# Controller_PCB_OPAMP.net
KiCad netlist of a schematic drawn in Altium Designer
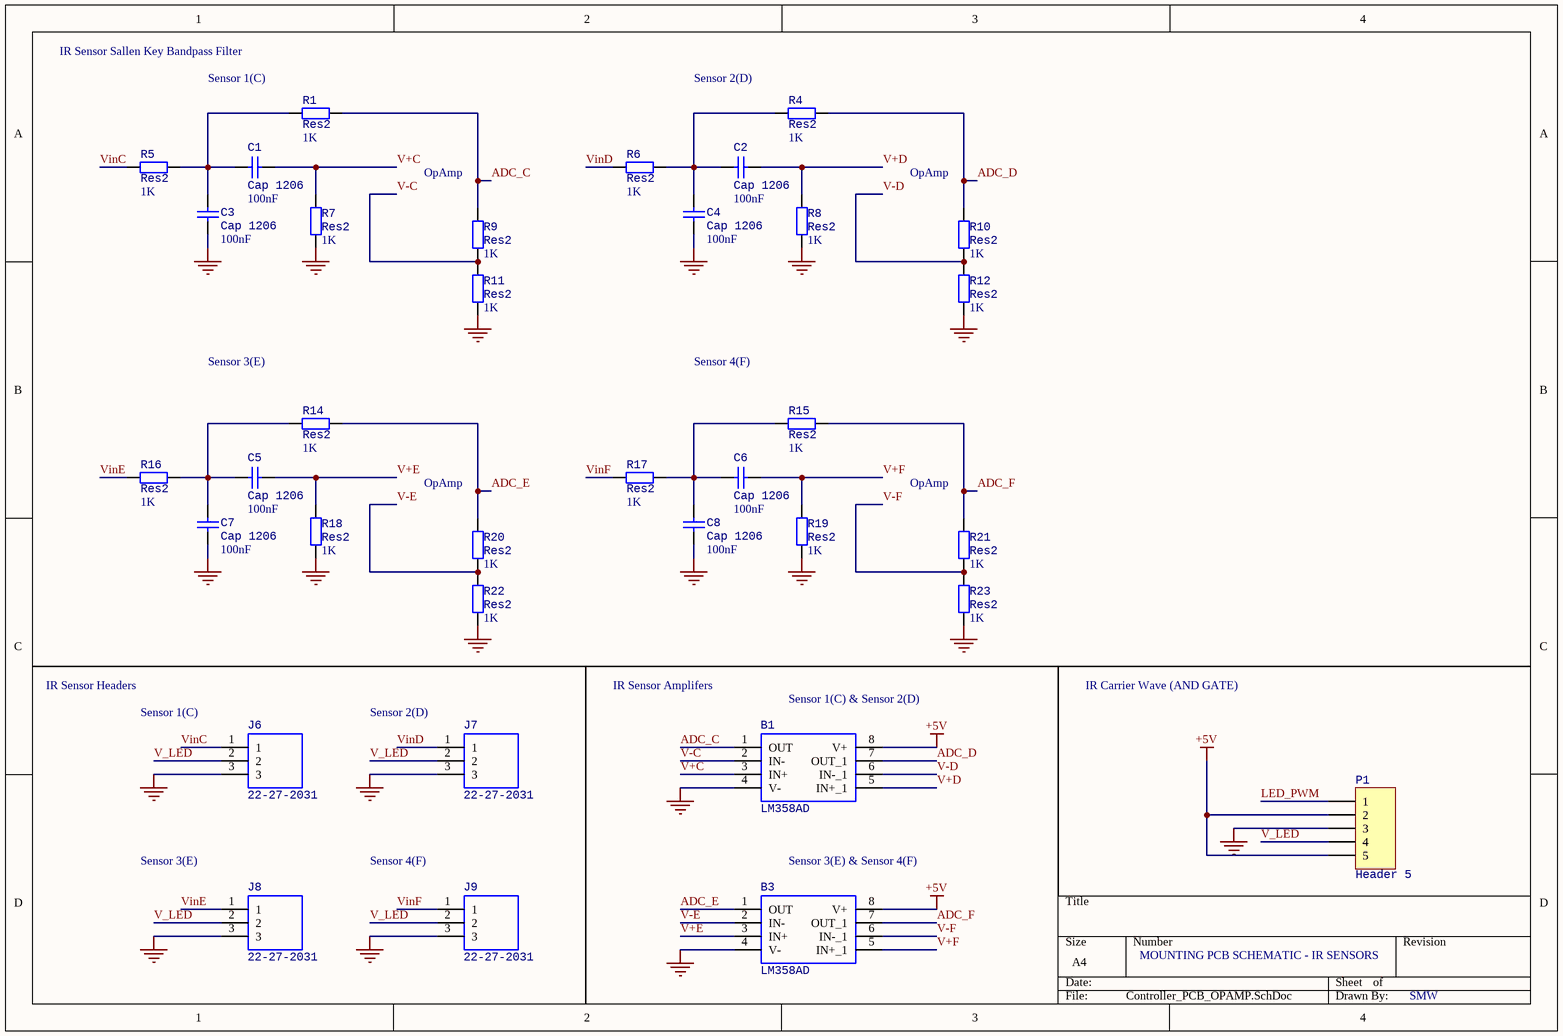
[diagram p0: Controller_PCB_OPAMP.SchDoc]

(export (version "E")
  (design (tool "Eeschema 10.0.6"))
  (components
    (comp (ref "B1")
      (value "LM358AD")
      (footprint "SOIC127P600X175-8N")
      (description "LM358AD, Dual Operational Amplifier 1.1MHz 5 to 28V, 8-Pin SO")
      (fields (field (name "RS PART NUMBER") "1657542"))
      (libsource (lib "LM358AD") (part "LM358AD"))
    )
    (comp (ref "B3")
      (value "LM358AD")
      (footprint "SOIC127P600X175-8N")
      (description "LM358AD, Dual Operational Amplifier 1.1MHz 5 to 28V, 8-Pin SO")
      (fields (field (name "RS PART NUMBER") "1657542"))
      (libsource (lib "LM358AD") (part "LM358AD"))
    )
    (comp (ref "C1")
      (value "Cap 1206")
      (footprint "C1206")
      (description "Capacitor (Semiconductor SIM Model)")
      (fields (field (name "ALTIUM_VALUE") "100nF") (field (name "PUBLISHER") "Altium Limited"))
      (libsource (lib "Miscellaneous Devices") (part "Cap Semi"))
    )
    (comp (ref "C2")
      (value "Cap 1206")
      (footprint "C1206")
      (description "Capacitor (Semiconductor SIM Model)")
      (fields (field (name "ALTIUM_VALUE") "100nF") (field (name "PUBLISHER") "Altium Limited"))
      (libsource (lib "Miscellaneous Devices") (part "Cap Semi"))
    )
    (comp (ref "C3")
      (value "Cap 1206")
      (footprint "C1206")
      (description "Capacitor (Semiconductor SIM Model)")
      (fields (field (name "ALTIUM_VALUE") "100nF") (field (name "PUBLISHER") "Altium Limited"))
      (libsource (lib "Miscellaneous Devices") (part "Cap Semi"))
    )
    (comp (ref "C4")
      (value "Cap 1206")
      (footprint "C1206")
      (description "Capacitor (Semiconductor SIM Model)")
      (fields (field (name "ALTIUM_VALUE") "100nF") (field (name "PUBLISHER") "Altium Limited"))
      (libsource (lib "Miscellaneous Devices") (part "Cap Semi"))
    )
    (comp (ref "C5")
      (value "Cap 1206")
      (footprint "C1206")
      (description "Capacitor (Semiconductor SIM Model)")
      (fields (field (name "ALTIUM_VALUE") "100nF") (field (name "PUBLISHER") "Altium Limited"))
      (libsource (lib "Miscellaneous Devices") (part "Cap Semi"))
    )
    (comp (ref "C6")
      (value "Cap 1206")
      (footprint "C1206")
      (description "Capacitor (Semiconductor SIM Model)")
      (fields (field (name "ALTIUM_VALUE") "100nF") (field (name "PUBLISHER") "Altium Limited"))
      (libsource (lib "Miscellaneous Devices") (part "Cap Semi"))
    )
    (comp (ref "C7")
      (value "Cap 1206")
      (footprint "C1206")
      (description "Capacitor (Semiconductor SIM Model)")
      (fields (field (name "ALTIUM_VALUE") "100nF") (field (name "PUBLISHER") "Altium Limited"))
      (libsource (lib "Miscellaneous Devices") (part "Cap Semi"))
    )
    (comp (ref "C8")
      (value "Cap 1206")
      (footprint "C1206")
      (description "Capacitor (Semiconductor SIM Model)")
      (fields (field (name "ALTIUM_VALUE") "100nF") (field (name "PUBLISHER") "Altium Limited"))
      (libsource (lib "Miscellaneous Devices") (part "Cap Semi"))
    )
    (comp (ref "J6")
      (value "22-27-2031")
      (footprint "SHDR3W64P0X254_1X3_762X580X1170P")
      (fields (field (name "RS PART NUMBER") "1707102"))
      (libsource (lib "22-27-2031") (part "22-27-2031"))
    )
    (comp (ref "J7")
      (value "22-27-2031")
      (footprint "SHDR3W64P0X254_1X3_762X580X1170P")
      (fields (field (name "RS PART NUMBER") "1707102"))
      (libsource (lib "22-27-2031") (part "22-27-2031"))
    )
    (comp (ref "J8")
      (value "22-27-2031")
      (footprint "SHDR3W64P0X254_1X3_762X580X1170P")
      (fields (field (name "RS PART NUMBER") "1707102"))
      (libsource (lib "22-27-2031") (part "22-27-2031"))
    )
    (comp (ref "J9")
      (value "22-27-2031")
      (footprint "SHDR3W64P0X254_1X3_762X580X1170P")
      (fields (field (name "RS PART NUMBER") "1707102"))
      (libsource (lib "22-27-2031") (part "22-27-2031"))
    )
    (comp (ref "P1")
      (value "Header 5")
      (footprint "SOT353-1")
      (description "Header, 5-Pin")
      (fields (field (name "PUBLISHER") "Altium Limited"))
      (libsource (lib "Miscellaneous Connectors") (part "Header 5"))
    )
    (comp (ref "R1")
      (value "Res2")
      (footprint "C1206")
      (description "Resistor")
      (fields (field (name "ALTIUM_VALUE") "1K") (field (name "PUBLISHER") "Altium Limited"))
      (libsource (lib "") (part "Res2_1"))
    )
    (comp (ref "R4")
      (value "Res2")
      (footprint "C1206")
      (description "Resistor")
      (fields (field (name "ALTIUM_VALUE") "1K") (field (name "PUBLISHER") "Altium Limited"))
      (libsource (lib "") (part "Res2_1"))
    )
    (comp (ref "R5")
      (value "Res2")
      (footprint "C1206")
      (description "Resistor")
      (fields (field (name "ALTIUM_VALUE") "1K") (field (name "PUBLISHER") "Altium Limited"))
      (libsource (lib "") (part "Res2_1"))
    )
    (comp (ref "R6")
      (value "Res2")
      (footprint "C1206")
      (description "Resistor")
      (fields (field (name "ALTIUM_VALUE") "1K") (field (name "PUBLISHER") "Altium Limited"))
      (libsource (lib "") (part "Res2_1"))
    )
    (comp (ref "R7")
      (value "Res2")
      (footprint "C1206")
      (description "Resistor")
      (fields (field (name "ALTIUM_VALUE") "1K") (field (name "PUBLISHER") "Altium Limited"))
      (libsource (lib "Miscellaneous Devices") (part "Res2"))
    )
    (comp (ref "R8")
      (value "Res2")
      (footprint "C1206")
      (description "Resistor")
      (fields (field (name "ALTIUM_VALUE") "1K") (field (name "PUBLISHER") "Altium Limited"))
      (libsource (lib "Miscellaneous Devices") (part "Res2"))
    )
    (comp (ref "R9")
      (value "Res2")
      (footprint "C1206")
      (description "Resistor")
      (fields (field (name "ALTIUM_VALUE") "1K") (field (name "PUBLISHER") "Altium Limited"))
      (libsource (lib "Miscellaneous Devices") (part "Res2"))
    )
    (comp (ref "R10")
      (value "Res2")
      (footprint "C1206")
      (description "Resistor")
      (fields (field (name "ALTIUM_VALUE") "1K") (field (name "PUBLISHER") "Altium Limited"))
      (libsource (lib "Miscellaneous Devices") (part "Res2"))
    )
    (comp (ref "R11")
      (value "Res2")
      (footprint "C1206")
      (description "Resistor")
      (fields (field (name "ALTIUM_VALUE") "1K") (field (name "PUBLISHER") "Altium Limited"))
      (libsource (lib "Miscellaneous Devices") (part "Res2"))
    )
    (comp (ref "R12")
      (value "Res2")
      (footprint "C1206")
      (description "Resistor")
      (fields (field (name "ALTIUM_VALUE") "1K") (field (name "PUBLISHER") "Altium Limited"))
      (libsource (lib "Miscellaneous Devices") (part "Res2"))
    )
    (comp (ref "R14")
      (value "Res2")
      (footprint "C1206")
      (description "Resistor")
      (fields (field (name "ALTIUM_VALUE") "1K") (field (name "PUBLISHER") "Altium Limited"))
      (libsource (lib "") (part "Res2_1"))
    )
    (comp (ref "R15")
      (value "Res2")
      (footprint "C1206")
      (description "Resistor")
      (fields (field (name "ALTIUM_VALUE") "1K") (field (name "PUBLISHER") "Altium Limited"))
      (libsource (lib "") (part "Res2_1"))
    )
    (comp (ref "R16")
      (value "Res2")
      (footprint "C1206")
      (description "Resistor")
      (fields (field (name "ALTIUM_VALUE") "1K") (field (name "PUBLISHER") "Altium Limited"))
      (libsource (lib "") (part "Res2_1"))
    )
    (comp (ref "R17")
      (value "Res2")
      (footprint "C1206")
      (description "Resistor")
      (fields (field (name "ALTIUM_VALUE") "1K") (field (name "PUBLISHER") "Altium Limited"))
      (libsource (lib "") (part "Res2_1"))
    )
    (comp (ref "R18")
      (value "Res2")
      (footprint "C1206")
      (description "Resistor")
      (fields (field (name "ALTIUM_VALUE") "1K") (field (name "PUBLISHER") "Altium Limited"))
      (libsource (lib "Miscellaneous Devices") (part "Res2"))
    )
    (comp (ref "R19")
      (value "Res2")
      (footprint "C1206")
      (description "Resistor")
      (fields (field (name "ALTIUM_VALUE") "1K") (field (name "PUBLISHER") "Altium Limited"))
      (libsource (lib "Miscellaneous Devices") (part "Res2"))
    )
    (comp (ref "R20")
      (value "Res2")
      (footprint "C1206")
      (description "Resistor")
      (fields (field (name "ALTIUM_VALUE") "1K") (field (name "PUBLISHER") "Altium Limited"))
      (libsource (lib "Miscellaneous Devices") (part "Res2"))
    )
    (comp (ref "R21")
      (value "Res2")
      (footprint "C1206")
      (description "Resistor")
      (fields (field (name "ALTIUM_VALUE") "1K") (field (name "PUBLISHER") "Altium Limited"))
      (libsource (lib "Miscellaneous Devices") (part "Res2"))
    )
    (comp (ref "R22")
      (value "Res2")
      (footprint "C1206")
      (description "Resistor")
      (fields (field (name "ALTIUM_VALUE") "1K") (field (name "PUBLISHER") "Altium Limited"))
      (libsource (lib "Miscellaneous Devices") (part "Res2"))
    )
    (comp (ref "R23")
      (value "Res2")
      (footprint "C1206")
      (description "Resistor")
      (fields (field (name "ALTIUM_VALUE") "1K") (field (name "PUBLISHER") "Altium Limited"))
      (libsource (lib "Miscellaneous Devices") (part "Res2"))
    )
  )
  (nets
    (net (code "1") (name "+5V") (class "Default")
      (node (ref "B1") (pin "8") (pinfunction "V+_8") (pintype "passive"))
      (node (ref "B3") (pin "8") (pinfunction "V+_8") (pintype "passive"))
      (node (ref "P1") (pin "2") (pinfunction "2_2") (pintype "passive"))
      (node (ref "P1") (pin "5") (pinfunction "5_5") (pintype "passive"))
    )
    (net (code "2") (name "/ADC_C") (class "Default")
      (node (ref "B1") (pin "1") (pinfunction "OUT_1") (pintype "passive"))
      (node (ref "R1") (pin "2") (pinfunction "2_2") (pintype "passive"))
      (node (ref "R9") (pin "2") (pinfunction "2_2") (pintype "passive"))
    )
    (net (code "3") (name "/ADC_D") (class "Default")
      (node (ref "B1") (pin "7") (pinfunction "OUT_1_7") (pintype "passive"))
      (node (ref "R10") (pin "2") (pinfunction "2_2") (pintype "passive"))
      (node (ref "R4") (pin "2") (pinfunction "2_2") (pintype "passive"))
    )
    (net (code "4") (name "/ADC_E") (class "Default")
      (node (ref "B3") (pin "1") (pinfunction "OUT_1") (pintype "passive"))
      (node (ref "R14") (pin "2") (pinfunction "2_2") (pintype "passive"))
      (node (ref "R20") (pin "2") (pinfunction "2_2") (pintype "passive"))
    )
    (net (code "5") (name "/ADC_F") (class "Default")
      (node (ref "B3") (pin "7") (pinfunction "OUT_1_7") (pintype "passive"))
      (node (ref "R15") (pin "2") (pinfunction "2_2") (pintype "passive"))
      (node (ref "R21") (pin "2") (pinfunction "2_2") (pintype "passive"))
    )
    (net (code "6") (name "/LED_PWM") (class "Default")
      (node (ref "P1") (pin "1") (pinfunction "1_1") (pintype "passive"))
    )
    (net (code "7") (name "/V+C") (class "Default")
      (node (ref "B1") (pin "3") (pinfunction "IN+_3") (pintype "passive"))
      (node (ref "C1") (pin "1") (pinfunction "1_1") (pintype "passive"))
      (node (ref "R7") (pin "2") (pinfunction "2_2") (pintype "passive"))
    )
    (net (code "8") (name "/V+D") (class "Default")
      (node (ref "B1") (pin "5") (pinfunction "IN+_1_5") (pintype "passive"))
      (node (ref "C2") (pin "1") (pinfunction "1_1") (pintype "passive"))
      (node (ref "R8") (pin "2") (pinfunction "2_2") (pintype "passive"))
    )
    (net (code "9") (name "/V+E") (class "Default")
      (node (ref "B3") (pin "3") (pinfunction "IN+_3") (pintype "passive"))
      (node (ref "C5") (pin "1") (pinfunction "1_1") (pintype "passive"))
      (node (ref "R18") (pin "2") (pinfunction "2_2") (pintype "passive"))
    )
    (net (code "10") (name "/V+F") (class "Default")
      (node (ref "B3") (pin "5") (pinfunction "IN+_1_5") (pintype "passive"))
      (node (ref "C6") (pin "1") (pinfunction "1_1") (pintype "passive"))
      (node (ref "R19") (pin "2") (pinfunction "2_2") (pintype "passive"))
    )
    (net (code "11") (name "/V-C") (class "Default")
      (node (ref "B1") (pin "2") (pinfunction "IN-_2") (pintype "passive"))
      (node (ref "R11") (pin "2") (pinfunction "2_2") (pintype "passive"))
      (node (ref "R9") (pin "1") (pinfunction "1_1") (pintype "passive"))
    )
    (net (code "12") (name "/V-D") (class "Default")
      (node (ref "B1") (pin "6") (pinfunction "IN-_1_6") (pintype "passive"))
      (node (ref "R10") (pin "1") (pinfunction "1_1") (pintype "passive"))
      (node (ref "R12") (pin "2") (pinfunction "2_2") (pintype "passive"))
    )
    (net (code "13") (name "/V-E") (class "Default")
      (node (ref "B3") (pin "2") (pinfunction "IN-_2") (pintype "passive"))
      (node (ref "R20") (pin "1") (pinfunction "1_1") (pintype "passive"))
      (node (ref "R22") (pin "2") (pinfunction "2_2") (pintype "passive"))
    )
    (net (code "14") (name "/V-F") (class "Default")
      (node (ref "B3") (pin "6") (pinfunction "IN-_1_6") (pintype "passive"))
      (node (ref "R21") (pin "1") (pinfunction "1_1") (pintype "passive"))
      (node (ref "R23") (pin "2") (pinfunction "2_2") (pintype "passive"))
    )
    (net (code "15") (name "/V_LED") (class "Default")
      (node (ref "J6") (pin "2") (pinfunction "2_2") (pintype "passive"))
      (node (ref "J7") (pin "2") (pinfunction "2_2") (pintype "passive"))
      (node (ref "J8") (pin "2") (pinfunction "2_2") (pintype "passive"))
      (node (ref "J9") (pin "2") (pinfunction "2_2") (pintype "passive"))
      (node (ref "P1") (pin "4") (pinfunction "4_4") (pintype "passive"))
    )
    (net (code "16") (name "/VinC") (class "Default")
      (node (ref "J6") (pin "1") (pinfunction "1_1") (pintype "passive"))
      (node (ref "R5") (pin "1") (pinfunction "1_1") (pintype "passive"))
    )
    (net (code "17") (name "/VinD") (class "Default")
      (node (ref "J7") (pin "1") (pinfunction "1_1") (pintype "passive"))
      (node (ref "R6") (pin "1") (pinfunction "1_1") (pintype "passive"))
    )
    (net (code "18") (name "/VinE") (class "Default")
      (node (ref "J8") (pin "1") (pinfunction "1_1") (pintype "passive"))
      (node (ref "R16") (pin "1") (pinfunction "1_1") (pintype "passive"))
    )
    (net (code "19") (name "/VinF") (class "Default")
      (node (ref "J9") (pin "1") (pinfunction "1_1") (pintype "passive"))
      (node (ref "R17") (pin "1") (pinfunction "1_1") (pintype "passive"))
    )
    (net (code "20") (name "GND") (class "Default")
      (node (ref "B1") (pin "4") (pinfunction "V-_4") (pintype "passive"))
      (node (ref "B3") (pin "4") (pinfunction "V-_4") (pintype "passive"))
      (node (ref "C3") (pin "1") (pinfunction "1_1") (pintype "passive"))
      (node (ref "C4") (pin "1") (pinfunction "1_1") (pintype "passive"))
      (node (ref "C7") (pin "1") (pinfunction "1_1") (pintype "passive"))
      (node (ref "C8") (pin "1") (pinfunction "1_1") (pintype "passive"))
      (node (ref "J6") (pin "3") (pinfunction "3_3") (pintype "passive"))
      (node (ref "J7") (pin "3") (pinfunction "3_3") (pintype "passive"))
      (node (ref "J8") (pin "3") (pinfunction "3_3") (pintype "passive"))
      (node (ref "J9") (pin "3") (pinfunction "3_3") (pintype "passive"))
      (node (ref "P1") (pin "3") (pinfunction "3_3") (pintype "passive"))
      (node (ref "R11") (pin "1") (pinfunction "1_1") (pintype "passive"))
      (node (ref "R12") (pin "1") (pinfunction "1_1") (pintype "passive"))
      (node (ref "R18") (pin "1") (pinfunction "1_1") (pintype "passive"))
      (node (ref "R19") (pin "1") (pinfunction "1_1") (pintype "passive"))
      (node (ref "R22") (pin "1") (pinfunction "1_1") (pintype "passive"))
      (node (ref "R23") (pin "1") (pinfunction "1_1") (pintype "passive"))
      (node (ref "R7") (pin "1") (pinfunction "1_1") (pintype "passive"))
      (node (ref "R8") (pin "1") (pinfunction "1_1") (pintype "passive"))
    )
    (net (code "21") (name "Net-(C1-Pad2)") (class "Default")
      (node (ref "C1") (pin "2") (pinfunction "2_2") (pintype "passive"))
      (node (ref "C3") (pin "2") (pinfunction "2_2") (pintype "passive"))
      (node (ref "R1") (pin "1") (pinfunction "1_1") (pintype "passive"))
      (node (ref "R5") (pin "2") (pinfunction "2_2") (pintype "passive"))
    )
    (net (code "22") (name "Net-(C2-Pad2)") (class "Default")
      (node (ref "C2") (pin "2") (pinfunction "2_2") (pintype "passive"))
      (node (ref "C4") (pin "2") (pinfunction "2_2") (pintype "passive"))
      (node (ref "R4") (pin "1") (pinfunction "1_1") (pintype "passive"))
      (node (ref "R6") (pin "2") (pinfunction "2_2") (pintype "passive"))
    )
    (net (code "23") (name "Net-(C5-Pad2)") (class "Default")
      (node (ref "C5") (pin "2") (pinfunction "2_2") (pintype "passive"))
      (node (ref "C7") (pin "2") (pinfunction "2_2") (pintype "passive"))
      (node (ref "R14") (pin "1") (pinfunction "1_1") (pintype "passive"))
      (node (ref "R16") (pin "2") (pinfunction "2_2") (pintype "passive"))
    )
    (net (code "24") (name "Net-(C6-Pad2)") (class "Default")
      (node (ref "C6") (pin "2") (pinfunction "2_2") (pintype "passive"))
      (node (ref "C8") (pin "2") (pinfunction "2_2") (pintype "passive"))
      (node (ref "R15") (pin "1") (pinfunction "1_1") (pintype "passive"))
      (node (ref "R17") (pin "2") (pinfunction "2_2") (pintype "passive"))
    )
  )
)
